# OpenMV.net
KiCad netlist of a schematic drawn in Altium Designer
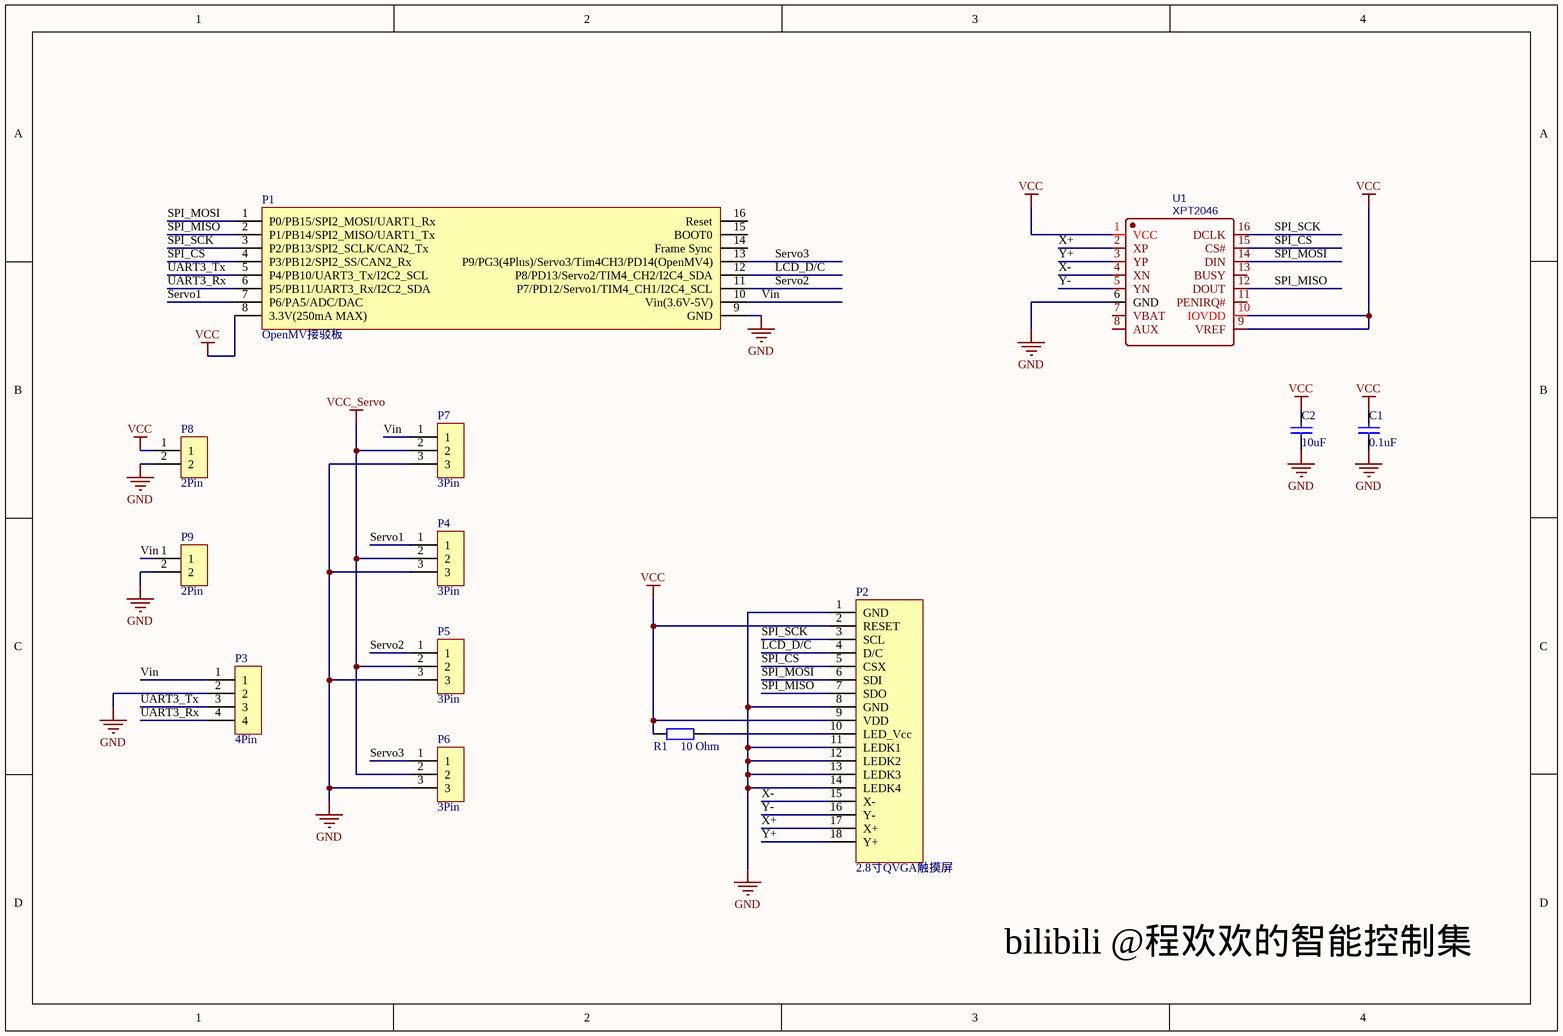
[diagram p0: OpenMV电阻屏扩展板.SchDoc]

(export (version "E")
  (design (tool "Eeschema 10.0.6"))
  (components
    (comp (ref "C1")
      (value "0.1uF")
      (footprint "0603")
      (description "Capacitor")
      (fields (field (name "PUBLISHER") "Altium Limited"))
      (libsource (lib "Miscellaneous Devices") (part "Cap"))
    )
    (comp (ref "C2")
      (value "10uF")
      (footprint "0805")
      (description "Capacitor")
      (fields (field (name "PUBLISHER") "Altium Limited"))
      (libsource (lib "Miscellaneous Devices") (part "Cap"))
    )
    (comp (ref "P1")
      (value "OpenMV接驳板")
      (footprint "OpenMV扩展版(贴片排母)")
      (libsource (lib "OpenMV接驳板") (part "OpenMV接驳板"))
    )
    (comp (ref "P2")
      (value "2.8寸QVGA触摸屏")
      (footprint "2.8寸电阻屏-修改版")
      (libsource (lib "2.8寸QVGA触摸屏") (part "2.8寸QVGA触摸屏"))
    )
    (comp (ref "P3") (value "4Pin") (footprint "4Pin-2.54") (libsource (lib "4Pin") (part "4Pin")))
    (comp (ref "P4") (value "3Pin") (footprint "3Pin-2.54") (libsource (lib "3Pin") (part "3Pin")))
    (comp (ref "P5") (value "3Pin") (footprint "3Pin-2.54") (libsource (lib "3Pin") (part "3Pin")))
    (comp (ref "P6") (value "3Pin") (footprint "3Pin-2.54") (libsource (lib "3Pin") (part "3Pin")))
    (comp (ref "P7") (value "3Pin") (footprint "3Pin-2.54") (libsource (lib "3Pin") (part "3Pin")))
    (comp (ref "P8") (value "2Pin") (footprint "2Pin-2.54") (libsource (lib "2Pin") (part "2Pin")))
    (comp (ref "P9") (value "2Pin") (footprint "2Pin-2.54") (libsource (lib "2Pin") (part "2Pin")))
    (comp (ref "R1")
      (value "10 Ohm")
      (footprint "0603")
      (description "Resistor")
      (fields (field (name "PUBLISHER") "Altium Limited"))
      (libsource (lib "Miscellaneous Devices") (part "Res2"))
    )
    (comp (ref "U1")
      (value "XPT2046")
      (footprint "TSSOP-16_L5.0")
      (fields (field (name "BOM_SUPPLIER PART") "C19076"))
      (libsource (lib "altium-import") (part "root_0_XPT2046_"))
    )
  )
  (nets
    (net (code "1") (name "/LCD_D{slash}C") (class "Default")
      (node (ref "P1") (pin "12") (pinfunction "P8/PD13/Servo2/TIM4_CH2/I2C4_SDA_12") (pintype "passive"))
      (node (ref "P2") (pin "4") (pinfunction "D/C_4") (pintype "passive"))
    )
    (net (code "2") (name "/SPI_CS") (class "Default")
      (node (ref "P1") (pin "4") (pinfunction "P3/PB12/SPI2_SS/CAN2_Rx_4") (pintype "passive"))
      (node (ref "P2") (pin "5") (pinfunction "CSX_5") (pintype "passive"))
      (node (ref "U1") (pin "15") (pinfunction "CS#_15") (pintype "passive"))
    )
    (net (code "3") (name "/SPI_MISO") (class "Default")
      (node (ref "P1") (pin "2") (pinfunction "P1/PB14/SPI2_MISO/UART1_Tx_2") (pintype "passive"))
      (node (ref "P2") (pin "7") (pinfunction "SDO_7") (pintype "passive"))
      (node (ref "U1") (pin "12") (pinfunction "DOUT_12") (pintype "passive"))
    )
    (net (code "4") (name "/SPI_MOSI") (class "Default")
      (node (ref "P1") (pin "1") (pinfunction "P0/PB15/SPI2_MOSI/UART1_Rx_1") (pintype "passive"))
      (node (ref "P2") (pin "6") (pinfunction "SDI_6") (pintype "passive"))
      (node (ref "U1") (pin "14") (pinfunction "DIN_14") (pintype "passive"))
    )
    (net (code "5") (name "/SPI_SCK") (class "Default")
      (node (ref "P1") (pin "3") (pinfunction "P2/PB13/SPI2_SCLK/CAN2_Tx_3") (pintype "passive"))
      (node (ref "P2") (pin "3") (pinfunction "SCL_3") (pintype "passive"))
      (node (ref "U1") (pin "16") (pinfunction "DCLK_16") (pintype "passive"))
    )
    (net (code "6") (name "/Servo1") (class "Default")
      (node (ref "P1") (pin "7") (pinfunction "P6/PA5/ADC/DAC_7") (pintype "passive"))
      (node (ref "P4") (pin "1") (pinfunction "1_1") (pintype "passive"))
    )
    (net (code "7") (name "/Servo2") (class "Default")
      (node (ref "P1") (pin "11") (pinfunction "P7/PD12/Servo1/TIM4_CH1/I2C4_SCL_11") (pintype "passive"))
      (node (ref "P5") (pin "1") (pinfunction "1_1") (pintype "passive"))
    )
    (net (code "8") (name "/Servo3") (class "Default")
      (node (ref "P1") (pin "13") (pinfunction "P9/PG3(4Plus)/Servo3/Tim4CH3/PD14(OpenMV4)_13") (pintype "passive"))
      (node (ref "P6") (pin "1") (pinfunction "1_1") (pintype "passive"))
    )
    (net (code "9") (name "/UART3_Rx") (class "Default")
      (node (ref "P1") (pin "6") (pinfunction "P5/PB11/UART3_Rx/I2C2_SDA_6") (pintype "passive"))
      (node (ref "P3") (pin "4") (pinfunction "4_4") (pintype "passive"))
    )
    (net (code "10") (name "/UART3_Tx") (class "Default")
      (node (ref "P1") (pin "5") (pinfunction "P4/PB10/UART3_Tx/I2C2_SCL_5") (pintype "passive"))
      (node (ref "P3") (pin "3") (pinfunction "3_3") (pintype "passive"))
    )
    (net (code "11") (name "/Vin") (class "Default")
      (node (ref "P1") (pin "10") (pinfunction "Vin(3.6V-5V)_10") (pintype "passive"))
      (node (ref "P3") (pin "1") (pinfunction "1_1") (pintype "passive"))
      (node (ref "P7") (pin "1") (pinfunction "1_1") (pintype "passive"))
      (node (ref "P9") (pin "1") (pinfunction "1_1") (pintype "passive"))
    )
    (net (code "12") (name "/X+") (class "Default")
      (node (ref "P2") (pin "17") (pinfunction "X+_17") (pintype "passive"))
      (node (ref "U1") (pin "2") (pinfunction "XP_2") (pintype "passive"))
    )
    (net (code "13") (name "/X-") (class "Default")
      (node (ref "P2") (pin "15") (pinfunction "X-_15") (pintype "passive"))
      (node (ref "U1") (pin "4") (pinfunction "XN_4") (pintype "passive"))
    )
    (net (code "14") (name "/Y+") (class "Default")
      (node (ref "P2") (pin "18") (pinfunction "Y+_18") (pintype "passive"))
      (node (ref "U1") (pin "3") (pinfunction "YP_3") (pintype "passive"))
    )
    (net (code "15") (name "/Y-") (class "Default")
      (node (ref "P2") (pin "16") (pinfunction "Y-_16") (pintype "passive"))
      (node (ref "U1") (pin "5") (pinfunction "YN_5") (pintype "passive"))
    )
    (net (code "16") (name "GND") (class "Default")
      (node (ref "C1") (pin "1") (pinfunction "1_1") (pintype "passive"))
      (node (ref "C2") (pin "1") (pinfunction "1_1") (pintype "passive"))
      (node (ref "P1") (pin "9") (pinfunction "GND_9") (pintype "passive"))
      (node (ref "P2") (pin "1") (pinfunction "GND_1") (pintype "passive"))
      (node (ref "P2") (pin "11") (pinfunction "LEDK1_11") (pintype "passive"))
      (node (ref "P2") (pin "12") (pinfunction "LEDK2_12") (pintype "passive"))
      (node (ref "P2") (pin "13") (pinfunction "LEDK3_13") (pintype "passive"))
      (node (ref "P2") (pin "14") (pinfunction "LEDK4_14") (pintype "passive"))
      (node (ref "P2") (pin "8") (pinfunction "GND_8") (pintype "passive"))
      (node (ref "P3") (pin "2") (pinfunction "2_2") (pintype "passive"))
      (node (ref "P4") (pin "3") (pinfunction "3_3") (pintype "passive"))
      (node (ref "P5") (pin "3") (pinfunction "3_3") (pintype "passive"))
      (node (ref "P6") (pin "3") (pinfunction "3_3") (pintype "passive"))
      (node (ref "P7") (pin "3") (pinfunction "3_3") (pintype "passive"))
      (node (ref "P8") (pin "2") (pinfunction "2_2") (pintype "passive"))
      (node (ref "P9") (pin "2") (pinfunction "2_2") (pintype "passive"))
      (node (ref "U1") (pin "6") (pinfunction "GND_6") (pintype "passive"))
    )
    (net (code "17") (name "Net-(P2-LED_Vcc)") (class "Default")
      (node (ref "P2") (pin "10") (pinfunction "LED_Vcc_10") (pintype "passive"))
      (node (ref "R1") (pin "2") (pinfunction "2_2") (pintype "passive"))
    )
    (net (code "18") (name "VCC") (class "Default")
      (node (ref "C1") (pin "2") (pinfunction "2_2") (pintype "passive"))
      (node (ref "C2") (pin "2") (pinfunction "2_2") (pintype "passive"))
      (node (ref "P1") (pin "8") (pinfunction "3.3V(250mA_MAX)_8") (pintype "passive"))
      (node (ref "P2") (pin "2") (pinfunction "RESET_2") (pintype "passive"))
      (node (ref "P2") (pin "9") (pinfunction "VDD_9") (pintype "passive"))
      (node (ref "P8") (pin "1") (pinfunction "1_1") (pintype "passive"))
      (node (ref "R1") (pin "1") (pinfunction "1_1") (pintype "passive"))
      (node (ref "U1") (pin "1") (pinfunction "VCC_1") (pintype "passive"))
      (node (ref "U1") (pin "10") (pinfunction "IOVDD_10") (pintype "passive"))
      (node (ref "U1") (pin "9") (pinfunction "VREF_9") (pintype "passive"))
    )
    (net (code "19") (name "VCC_Servo") (class "Default")
      (node (ref "P4") (pin "2") (pinfunction "2_2") (pintype "passive"))
      (node (ref "P5") (pin "2") (pinfunction "2_2") (pintype "passive"))
      (node (ref "P6") (pin "2") (pinfunction "2_2") (pintype "passive"))
      (node (ref "P7") (pin "2") (pinfunction "2_2") (pintype "passive"))
    )
    (net (code "20") (name "unconnected-(P1-BOOT0-Pad15)") (class "Default")
      (node (ref "P1") (pin "15") (pinfunction "BOOT0_15") (pintype "passive"))
    )
    (net (code "21") (name "unconnected-(P1-Frame_Sync-Pad14)") (class "Default")
      (node (ref "P1") (pin "14") (pinfunction "Frame_Sync_14") (pintype "passive"))
    )
    (net (code "22") (name "unconnected-(P1-Reset-Pad16)") (class "Default")
      (node (ref "P1") (pin "16") (pinfunction "Reset_16") (pintype "passive"))
    )
    (net (code "23") (name "unconnected-(U1-AUX-Pad8)") (class "Default")
      (node (ref "U1") (pin "8") (pinfunction "AUX_8") (pintype "passive"))
    )
    (net (code "24") (name "unconnected-(U1-BUSY-Pad13)") (class "Default")
      (node (ref "U1") (pin "13") (pinfunction "BUSY_13") (pintype "passive"))
    )
    (net (code "25") (name "unconnected-(U1-PENIRQ#-Pad11)") (class "Default")
      (node (ref "U1") (pin "11") (pinfunction "PENIRQ#_11") (pintype "passive"))
    )
    (net (code "26") (name "unconnected-(U1-VBAT-Pad7)") (class "Default")
      (node (ref "U1") (pin "7") (pinfunction "VBAT_7") (pintype "passive"))
    )
  )
)
